# Interface.net
KiCad netlist of a schematic drawn in Altium Designer
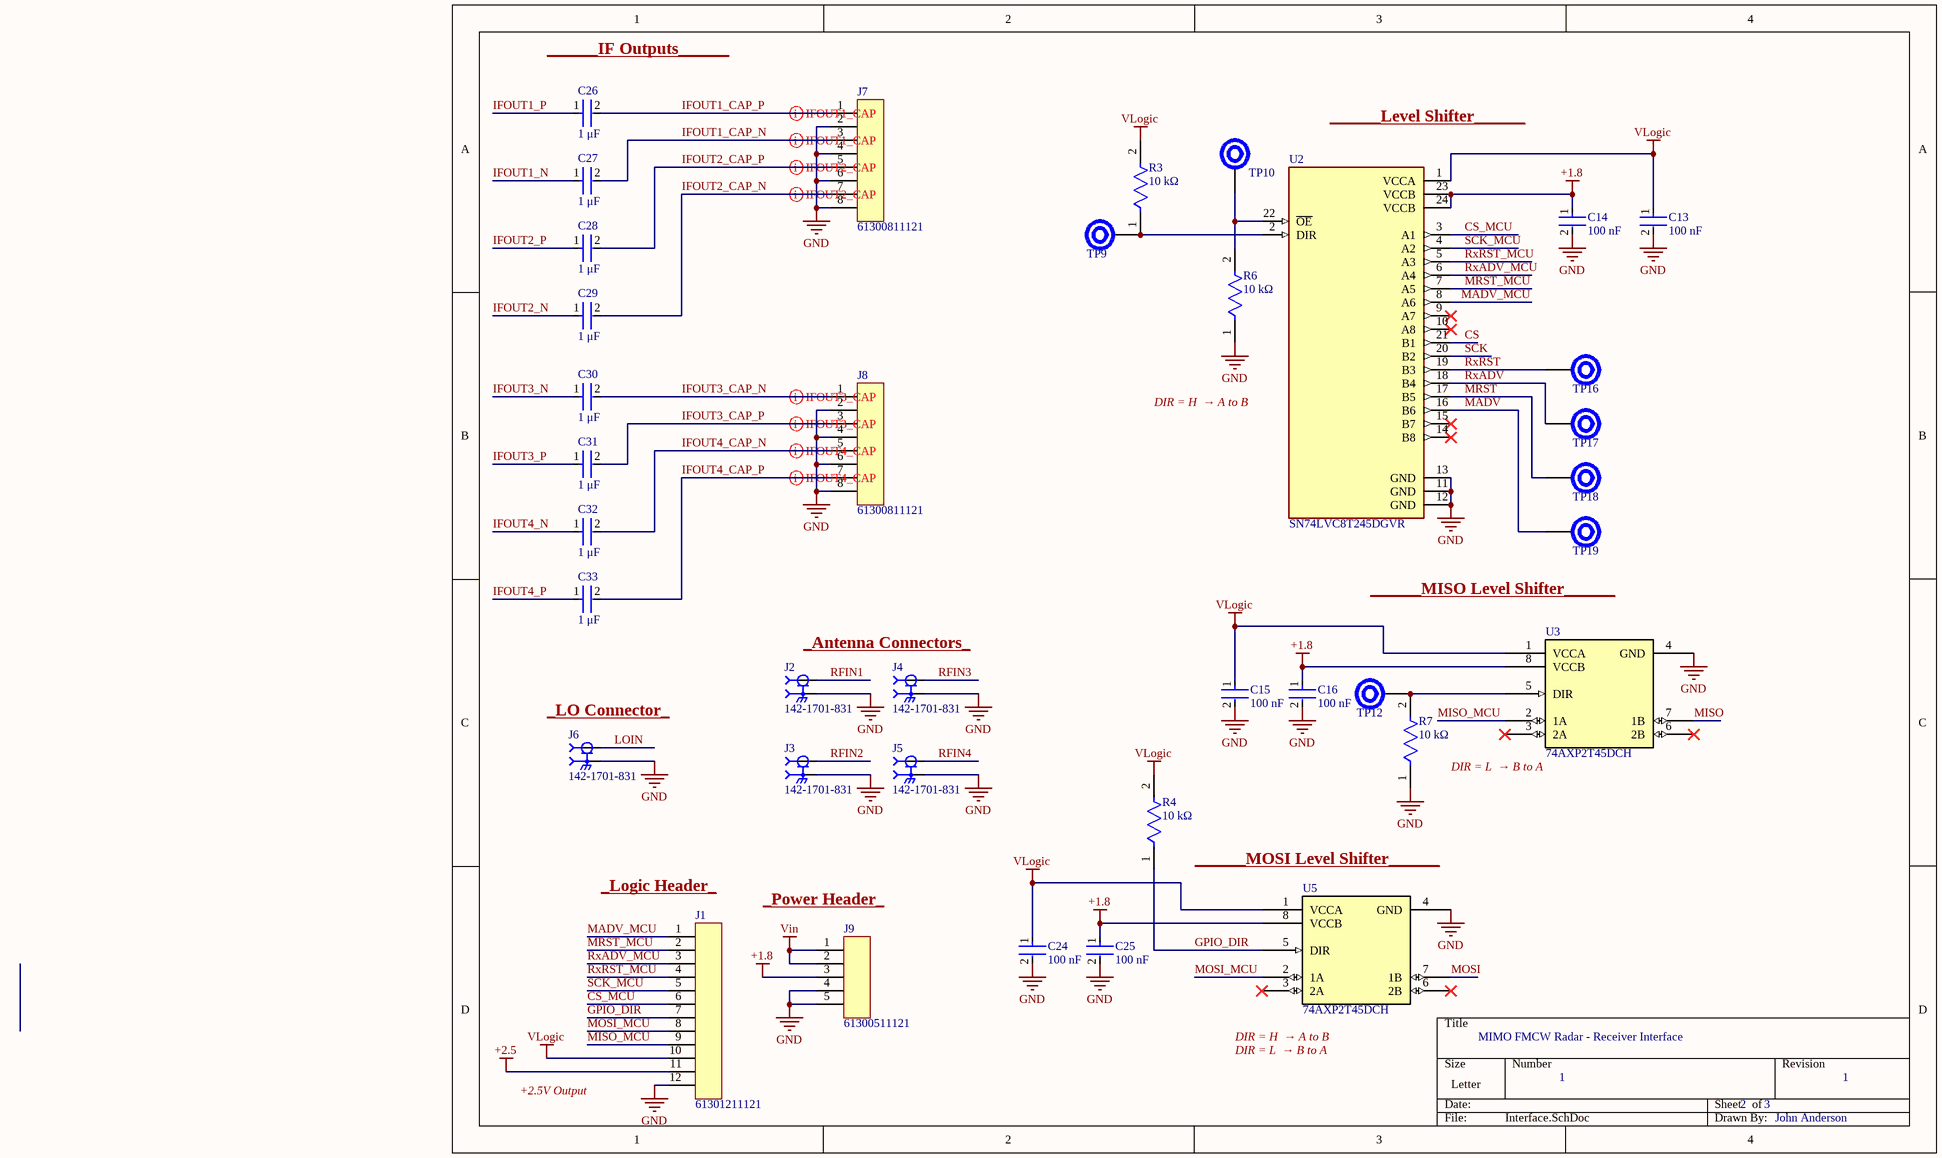
[diagram p0: Interface.SchDoc]

(export (version "E")
  (design (tool "Eeschema 10.0.6"))
  (components
    (comp (ref "C13")
      (value "100 nF")
      (footprint "FP-CGA3E-0_3-0_1-MFG")
      (libsource (lib "Power Pullers") (part "b4654b650e69147ec39a6b967a45e02"))
    )
    (comp (ref "C14")
      (value "100 nF")
      (footprint "FP-CGA3E-0_3-0_1-MFG")
      (libsource (lib "Power Pullers") (part "b4654b650e69147ec39a6b967a45e02"))
    )
    (comp (ref "C15")
      (value "100 nF")
      (footprint "FP-CGA3E-0_3-0_1-MFG")
      (libsource (lib "Power Pullers") (part "b4654b650e69147ec39a6b967a45e02"))
    )
    (comp (ref "C16")
      (value "100 nF")
      (footprint "FP-CGA3E-0_3-0_1-MFG")
      (libsource (lib "Power Pullers") (part "b4654b650e69147ec39a6b967a45e02"))
    )
    (comp (ref "C24")
      (value "100 nF")
      (footprint "FP-CGA3E-0_3-0_1-MFG")
      (libsource (lib "Power Pullers") (part "b4654b650e69147ec39a6b967a45e02"))
    )
    (comp (ref "C25")
      (value "100 nF")
      (footprint "FP-CGA3E-0_3-0_1-MFG")
      (libsource (lib "Power Pullers") (part "b4654b650e69147ec39a6b967a45e02"))
    )
    (comp (ref "C26")
      (value "1 μF")
      (footprint "FP-0603-L_1_6_0_15-W_0_8-MFG")
      (libsource (lib "Power Pullers") (part "11868f565c42a9108669ba33697ecf6"))
    )
    (comp (ref "C27")
      (value "1 μF")
      (footprint "FP-0603-L_1_6_0_15-W_0_8-MFG")
      (libsource (lib "Power Pullers") (part "11868f565c42a9108669ba33697ecf6"))
    )
    (comp (ref "C28")
      (value "1 μF")
      (footprint "FP-0603-L_1_6_0_15-W_0_8-MFG")
      (libsource (lib "Power Pullers") (part "11868f565c42a9108669ba33697ecf6"))
    )
    (comp (ref "C29")
      (value "1 μF")
      (footprint "FP-0603-L_1_6_0_15-W_0_8-MFG")
      (libsource (lib "Power Pullers") (part "11868f565c42a9108669ba33697ecf6"))
    )
    (comp (ref "C30")
      (value "1 μF")
      (footprint "FP-0603-L_1_6_0_15-W_0_8-MFG")
      (libsource (lib "Power Pullers") (part "11868f565c42a9108669ba33697ecf6"))
    )
    (comp (ref "C31")
      (value "1 μF")
      (footprint "FP-0603-L_1_6_0_15-W_0_8-MFG")
      (libsource (lib "Power Pullers") (part "11868f565c42a9108669ba33697ecf6"))
    )
    (comp (ref "C32")
      (value "1 μF")
      (footprint "FP-0603-L_1_6_0_15-W_0_8-MFG")
      (libsource (lib "Power Pullers") (part "11868f565c42a9108669ba33697ecf6"))
    )
    (comp (ref "C33")
      (value "1 μF")
      (footprint "FP-0603-L_1_6_0_15-W_0_8-MFG")
      (libsource (lib "Power Pullers") (part "11868f565c42a9108669ba33697ecf6"))
    )
    (comp (ref "J1")
      (value "61301211121")
      (footprint "61301211121")
      (description "THT Vertical Pin Header WR-PHD, Pitch 2.54 mm, Single Row, 12 pins")
      (libsource (lib "Power Pullers") (part "Header_Male_1R_12P"))
    )
    (comp (ref "J2")
      (value "142-1701-831")
      (footprint "142-1701-831-Footprint-1")
      (description "RF SMA Connector, 1 Contact(s), Female, Board Mount, Surface Mount Terminal, Locking, Jack")
      (libsource (lib "Power Pullers") (part "142-1701-831-Symbol-1"))
    )
    (comp (ref "J3")
      (value "142-1701-831")
      (footprint "142-1701-831-Footprint-1")
      (description "RF SMA Connector, 1 Contact(s), Female, Board Mount, Surface Mount Terminal, Locking, Jack")
      (libsource (lib "Power Pullers") (part "142-1701-831-Symbol-1"))
    )
    (comp (ref "J4")
      (value "142-1701-831")
      (footprint "142-1701-831-Footprint-1")
      (description "RF SMA Connector, 1 Contact(s), Female, Board Mount, Surface Mount Terminal, Locking, Jack")
      (libsource (lib "Power Pullers") (part "142-1701-831-Symbol-1"))
    )
    (comp (ref "J5")
      (value "142-1701-831")
      (footprint "142-1701-831-Footprint-1")
      (description "RF SMA Connector, 1 Contact(s), Female, Board Mount, Surface Mount Terminal, Locking, Jack")
      (libsource (lib "Power Pullers") (part "142-1701-831-Symbol-1"))
    )
    (comp (ref "J6")
      (value "142-1701-831")
      (footprint "142-1701-831-Footprint-1")
      (description "RF SMA Connector, 1 Contact(s), Female, Board Mount, Surface Mount Terminal, Locking, Jack")
      (libsource (lib "Power Pullers") (part "142-1701-831-Symbol-1"))
    )
    (comp (ref "J7")
      (value "61300811121")
      (footprint "61300811121")
      (description "THT Vertical Pin Header WR-PHD, Pitch 2.54 mm, Single Row, 8 pins")
      (libsource (lib "Power Pullers") (part "Header_Male_1R_08P"))
    )
    (comp (ref "J8")
      (value "61300811121")
      (footprint "61300811121")
      (description "THT Vertical Pin Header WR-PHD, Pitch 2.54 mm, Single Row, 8 pins")
      (libsource (lib "Power Pullers") (part "Header_Male_1R_08P"))
    )
    (comp (ref "J9")
      (value "61300511121")
      (footprint "61300511121")
      (description "THT Vertical Pin Header WR-PHD, Pitch 2.54 mm, Single Row, 5 pins")
      (libsource (lib "Power Pullers") (part "Header_Male_1R_05P"))
    )
    (comp (ref "R3")
      (value "10 kΩ")
      (footprint "FP-RC0603-0_55-IPC_C")
      (fields (field (name "POWER") "100mW") (field (name "TOLERANCE") "1%"))
      (libsource (lib "Power Pullers") (part "1029c3af85768c4190bb7ad29bc67b5"))
    )
    (comp (ref "R4")
      (value "10 kΩ")
      (footprint "FP-RC0603-0_55-IPC_C")
      (fields (field (name "POWER") "100mW") (field (name "TOLERANCE") "1%"))
      (libsource (lib "Power Pullers") (part "1029c3af85768c4190bb7ad29bc67b5"))
    )
    (comp (ref "R6")
      (value "10 kΩ")
      (footprint "FP-RC0603-0_55-IPC_C")
      (fields (field (name "POWER") "100mW") (field (name "TOLERANCE") "1%"))
      (libsource (lib "Power Pullers") (part "1029c3af85768c4190bb7ad29bc67b5"))
    )
    (comp (ref "R7")
      (value "10 kΩ")
      (footprint "FP-RC0603-0_55-IPC_C")
      (fields (field (name "POWER") "100mW") (field (name "TOLERANCE") "1%"))
      (libsource (lib "Power Pullers") (part "1029c3af85768c4190bb7ad29bc67b5"))
    )
    (comp (ref "TP9")
      (value "Test Point - 32 mil")
      (footprint "Test Point - 32 mil-Footprint-1")
      (description "32 mil (0.8 mm) test point.")
      (libsource (lib "Power Pullers") (part "Test Point - 32 mil-Symbol-1"))
    )
    (comp (ref "TP10")
      (value "Test Point - 32 mil")
      (footprint "Test Point - 32 mil-Footprint-1")
      (description "32 mil (0.8 mm) test point.")
      (libsource (lib "Power Pullers") (part "Test Point - 32 mil-Symbol-1"))
    )
    (comp (ref "TP12")
      (value "Test Point - 32 mil")
      (footprint "Test Point - 32 mil-Footprint-1")
      (description "32 mil (0.8 mm) test point.")
      (libsource (lib "Power Pullers") (part "Test Point - 32 mil-Symbol-1"))
    )
    (comp (ref "TP16")
      (value "Test Point - 32 mil")
      (footprint "Test Point - 32 mil-Footprint-1")
      (description "32 mil (0.8 mm) test point.")
      (libsource (lib "Power Pullers") (part "Test Point - 32 mil-Symbol-1"))
    )
    (comp (ref "TP17")
      (value "Test Point - 32 mil")
      (footprint "Test Point - 32 mil-Footprint-1")
      (description "32 mil (0.8 mm) test point.")
      (libsource (lib "Power Pullers") (part "Test Point - 32 mil-Symbol-1"))
    )
    (comp (ref "TP18")
      (value "Test Point - 32 mil")
      (footprint "Test Point - 32 mil-Footprint-1")
      (description "32 mil (0.8 mm) test point.")
      (libsource (lib "Power Pullers") (part "Test Point - 32 mil-Symbol-1"))
    )
    (comp (ref "TP19")
      (value "Test Point - 32 mil")
      (footprint "Test Point - 32 mil-Footprint-1")
      (description "32 mil (0.8 mm) test point.")
      (libsource (lib "Power Pullers") (part "Test Point - 32 mil-Symbol-1"))
    )
    (comp (ref "U2")
      (value "SN74LVC8T245DGVR")
      (footprint "SN74LVC8T245DGVR-Footprint-1")
      (description "IC BUS TRANSCVR 8BIT 24TVSOP / Voltage Level Translator 8-CH Bidirectional 24-Pin TVSOP T/R")
      (libsource (lib "Power Pullers") (part "SN74LVC8T245DGVR-Symbol-1"))
    )
    (comp (ref "U3")
      (value "74AXP2T45DCH")
      (footprint "74AXP2T45DCH-Footprint-1")
      (description "Dual Supply Level Translator 2-bit Bidirectional 0.95V to 5.5V 8-Pin VSSOP")
      (libsource (lib "Power Pullers") (part "74AXP2T45DCH-Symbol-1"))
    )
    (comp (ref "U5")
      (value "74AXP2T45DCH")
      (footprint "74AXP2T45DCH-Footprint-1")
      (description "Dual Supply Level Translator 2-bit Bidirectional 0.95V to 5.5V 8-Pin VSSOP")
      (libsource (lib "Power Pullers") (part "74AXP2T45DCH-Symbol-1"))
    )
  )
  (nets
    (net (code "1") (name "+1.8") (class "Default")
      (node (ref "C14") (pin "1") (pinfunction "1_1") (pintype "passive"))
      (node (ref "C16") (pin "1") (pinfunction "1_1") (pintype "passive"))
      (node (ref "C25") (pin "1") (pinfunction "1_1") (pintype "passive"))
      (node (ref "J9") (pin "3") (pinfunction "3_3") (pintype "passive"))
      (node (ref "U2") (pin "23") (pinfunction "VCCB_23") (pintype "power_in"))
      (node (ref "U2") (pin "24") (pinfunction "VCCB_24") (pintype "power_in"))
      (node (ref "U3") (pin "8") (pinfunction "VCCB_8") (pintype "power_in"))
      (node (ref "U5") (pin "8") (pinfunction "VCCB_8") (pintype "power_in"))
    )
    (net (code "2") (name "+2.5") (class "Default")
      (node (ref "J1") (pin "11") (pinfunction "11_11") (pintype "passive"))
    )
    (net (code "3") (name "/CS") (class "Default")
      (node (ref "U2") (pin "21") (pinfunction "B1_21") (pintype "output"))
    )
    (net (code "4") (name "/CS_MCU") (class "Default")
      (node (ref "J1") (pin "6") (pinfunction "6_6") (pintype "passive"))
      (node (ref "U2") (pin "3") (pinfunction "A1_3") (pintype "output"))
    )
    (net (code "5") (name "/GPIO_DIR") (class "Default")
      (node (ref "J1") (pin "7") (pinfunction "7_7") (pintype "passive"))
      (node (ref "R4") (pin "1") (pinfunction "1_1") (pintype "passive"))
      (node (ref "U5") (pin "5") (pinfunction "DIR_5") (pintype "input"))
    )
    (net (code "6") (name "/IFOUT1_CAP_N") (class "Default")
      (node (ref "C27") (pin "2") (pinfunction "2_2") (pintype "passive"))
      (node (ref "J7") (pin "3") (pinfunction "3_3") (pintype "passive"))
    )
    (net (code "7") (name "/IFOUT1_CAP_P") (class "Default")
      (node (ref "C26") (pin "2") (pinfunction "2_2") (pintype "passive"))
      (node (ref "J7") (pin "1") (pinfunction "1_1") (pintype "passive"))
    )
    (net (code "8") (name "/IFOUT1_N") (class "Default")
      (node (ref "C27") (pin "1") (pinfunction "1_1") (pintype "passive"))
    )
    (net (code "9") (name "/IFOUT1_P") (class "Default")
      (node (ref "C26") (pin "1") (pinfunction "1_1") (pintype "passive"))
    )
    (net (code "10") (name "/IFOUT2_CAP_N") (class "Default")
      (node (ref "C29") (pin "2") (pinfunction "2_2") (pintype "passive"))
      (node (ref "J7") (pin "7") (pinfunction "7_7") (pintype "passive"))
    )
    (net (code "11") (name "/IFOUT2_CAP_P") (class "Default")
      (node (ref "C28") (pin "2") (pinfunction "2_2") (pintype "passive"))
      (node (ref "J7") (pin "5") (pinfunction "5_5") (pintype "passive"))
    )
    (net (code "12") (name "/IFOUT2_N") (class "Default")
      (node (ref "C29") (pin "1") (pinfunction "1_1") (pintype "passive"))
    )
    (net (code "13") (name "/IFOUT2_P") (class "Default")
      (node (ref "C28") (pin "1") (pinfunction "1_1") (pintype "passive"))
    )
    (net (code "14") (name "/IFOUT3_CAP_N") (class "Default")
      (node (ref "C30") (pin "2") (pinfunction "2_2") (pintype "passive"))
      (node (ref "J8") (pin "1") (pinfunction "1_1") (pintype "passive"))
    )
    (net (code "15") (name "/IFOUT3_CAP_P") (class "Default")
      (node (ref "C31") (pin "2") (pinfunction "2_2") (pintype "passive"))
      (node (ref "J8") (pin "3") (pinfunction "3_3") (pintype "passive"))
    )
    (net (code "16") (name "/IFOUT3_N") (class "Default")
      (node (ref "C30") (pin "1") (pinfunction "1_1") (pintype "passive"))
    )
    (net (code "17") (name "/IFOUT3_P") (class "Default")
      (node (ref "C31") (pin "1") (pinfunction "1_1") (pintype "passive"))
    )
    (net (code "18") (name "/IFOUT4_CAP_N") (class "Default")
      (node (ref "C32") (pin "2") (pinfunction "2_2") (pintype "passive"))
      (node (ref "J8") (pin "5") (pinfunction "5_5") (pintype "passive"))
    )
    (net (code "19") (name "/IFOUT4_CAP_P") (class "Default")
      (node (ref "C33") (pin "2") (pinfunction "2_2") (pintype "passive"))
      (node (ref "J8") (pin "7") (pinfunction "7_7") (pintype "passive"))
    )
    (net (code "20") (name "/IFOUT4_N") (class "Default")
      (node (ref "C32") (pin "1") (pinfunction "1_1") (pintype "passive"))
    )
    (net (code "21") (name "/IFOUT4_P") (class "Default")
      (node (ref "C33") (pin "1") (pinfunction "1_1") (pintype "passive"))
    )
    (net (code "22") (name "/LOIN") (class "Default")
      (node (ref "J6") (pin "1") (pinfunction "SIG_1") (pintype "passive"))
    )
    (net (code "23") (name "/MADV") (class "Default")
      (node (ref "TP19") (pin "1") (pinfunction "1_1") (pintype "passive"))
      (node (ref "U2") (pin "16") (pinfunction "B6_16") (pintype "output"))
    )
    (net (code "24") (name "/MADV_MCU") (class "Default")
      (node (ref "J1") (pin "1") (pinfunction "1_1") (pintype "passive"))
      (node (ref "U2") (pin "8") (pinfunction "A6_8") (pintype "output"))
    )
    (net (code "25") (name "/MISO") (class "Default")
      (node (ref "U3") (pin "7") (pinfunction "1B_7") (pintype "bidirectional"))
    )
    (net (code "26") (name "/MISO_MCU") (class "Default")
      (node (ref "J1") (pin "9") (pinfunction "9_9") (pintype "passive"))
      (node (ref "U3") (pin "2") (pinfunction "1A_2") (pintype "bidirectional"))
    )
    (net (code "27") (name "/MOSI") (class "Default")
      (node (ref "U5") (pin "7") (pinfunction "1B_7") (pintype "bidirectional"))
    )
    (net (code "28") (name "/MOSI_MCU") (class "Default")
      (node (ref "J1") (pin "8") (pinfunction "8_8") (pintype "passive"))
      (node (ref "U5") (pin "2") (pinfunction "1A_2") (pintype "bidirectional"))
    )
    (net (code "29") (name "/MRST") (class "Default")
      (node (ref "TP18") (pin "1") (pinfunction "1_1") (pintype "passive"))
      (node (ref "U2") (pin "17") (pinfunction "B5_17") (pintype "output"))
    )
    (net (code "30") (name "/MRST_MCU") (class "Default")
      (node (ref "J1") (pin "2") (pinfunction "2_2") (pintype "passive"))
      (node (ref "U2") (pin "7") (pinfunction "A5_7") (pintype "output"))
    )
    (net (code "31") (name "/RFIN1") (class "Default")
      (node (ref "J2") (pin "1") (pinfunction "SIG_1") (pintype "passive"))
    )
    (net (code "32") (name "/RFIN2") (class "Default")
      (node (ref "J3") (pin "1") (pinfunction "SIG_1") (pintype "passive"))
    )
    (net (code "33") (name "/RFIN3") (class "Default")
      (node (ref "J4") (pin "1") (pinfunction "SIG_1") (pintype "passive"))
    )
    (net (code "34") (name "/RFIN4") (class "Default")
      (node (ref "J5") (pin "1") (pinfunction "SIG_1") (pintype "passive"))
    )
    (net (code "35") (name "/RxADV") (class "Default")
      (node (ref "TP17") (pin "1") (pinfunction "1_1") (pintype "passive"))
      (node (ref "U2") (pin "18") (pinfunction "B4_18") (pintype "output"))
    )
    (net (code "36") (name "/RxADV_MCU") (class "Default")
      (node (ref "J1") (pin "3") (pinfunction "3_3") (pintype "passive"))
      (node (ref "U2") (pin "6") (pinfunction "A4_6") (pintype "output"))
    )
    (net (code "37") (name "/RxRST") (class "Default")
      (node (ref "TP16") (pin "1") (pinfunction "1_1") (pintype "passive"))
      (node (ref "U2") (pin "19") (pinfunction "B3_19") (pintype "output"))
    )
    (net (code "38") (name "/RxRST_MCU") (class "Default")
      (node (ref "J1") (pin "4") (pinfunction "4_4") (pintype "passive"))
      (node (ref "U2") (pin "5") (pinfunction "A3_5") (pintype "output"))
    )
    (net (code "39") (name "/SCK") (class "Default")
      (node (ref "U2") (pin "20") (pinfunction "B2_20") (pintype "output"))
    )
    (net (code "40") (name "/SCK_MCU") (class "Default")
      (node (ref "J1") (pin "5") (pinfunction "5_5") (pintype "passive"))
      (node (ref "U2") (pin "4") (pinfunction "A2_4") (pintype "output"))
    )
    (net (code "41") (name "GND") (class "Default")
      (node (ref "C13") (pin "2") (pinfunction "2_2") (pintype "passive"))
      (node (ref "C14") (pin "2") (pinfunction "2_2") (pintype "passive"))
      (node (ref "C15") (pin "2") (pinfunction "2_2") (pintype "passive"))
      (node (ref "C16") (pin "2") (pinfunction "2_2") (pintype "passive"))
      (node (ref "C24") (pin "2") (pinfunction "2_2") (pintype "passive"))
      (node (ref "C25") (pin "2") (pinfunction "2_2") (pintype "passive"))
      (node (ref "J1") (pin "12") (pinfunction "12_12") (pintype "passive"))
      (node (ref "J2") (pin "2") (pinfunction "GND_2") (pintype "power_in"))
      (node (ref "J3") (pin "2") (pinfunction "GND_2") (pintype "power_in"))
      (node (ref "J4") (pin "2") (pinfunction "GND_2") (pintype "power_in"))
      (node (ref "J5") (pin "2") (pinfunction "GND_2") (pintype "power_in"))
      (node (ref "J6") (pin "2") (pinfunction "GND_2") (pintype "power_in"))
      (node (ref "J7") (pin "2") (pinfunction "2_2") (pintype "passive"))
      (node (ref "J7") (pin "4") (pinfunction "4_4") (pintype "passive"))
      (node (ref "J7") (pin "6") (pinfunction "6_6") (pintype "passive"))
      (node (ref "J7") (pin "8") (pinfunction "8_8") (pintype "passive"))
      (node (ref "J8") (pin "2") (pinfunction "2_2") (pintype "passive"))
      (node (ref "J8") (pin "4") (pinfunction "4_4") (pintype "passive"))
      (node (ref "J8") (pin "6") (pinfunction "6_6") (pintype "passive"))
      (node (ref "J8") (pin "8") (pinfunction "8_8") (pintype "passive"))
      (node (ref "J9") (pin "4") (pinfunction "4_4") (pintype "passive"))
      (node (ref "J9") (pin "5") (pinfunction "5_5") (pintype "passive"))
      (node (ref "R6") (pin "1") (pinfunction "1_1") (pintype "passive"))
      (node (ref "R7") (pin "1") (pinfunction "1_1") (pintype "passive"))
      (node (ref "U2") (pin "11") (pinfunction "GND_11") (pintype "power_in"))
      (node (ref "U2") (pin "12") (pinfunction "GND_12") (pintype "power_in"))
      (node (ref "U2") (pin "13") (pinfunction "GND_13") (pintype "power_in"))
      (node (ref "U3") (pin "4") (pinfunction "GND_4") (pintype "power_in"))
      (node (ref "U5") (pin "4") (pinfunction "GND_4") (pintype "power_in"))
    )
    (net (code "42") (name "Net-(U2-DIR)") (class "Default")
      (node (ref "R3") (pin "1") (pinfunction "1_1") (pintype "passive"))
      (node (ref "TP9") (pin "1") (pinfunction "1_1") (pintype "passive"))
      (node (ref "U2") (pin "2") (pinfunction "DIR_2") (pintype "input"))
    )
    (net (code "43") (name "Net-(U2-~{OE})") (class "Default")
      (node (ref "R6") (pin "2") (pinfunction "2_2") (pintype "passive"))
      (node (ref "TP10") (pin "1") (pinfunction "1_1") (pintype "passive"))
      (node (ref "U2") (pin "22") (pinfunction "~{OE}_22") (pintype "input"))
    )
    (net (code "44") (name "Net-(U3-DIR)") (class "Default")
      (node (ref "R7") (pin "2") (pinfunction "2_2") (pintype "passive"))
      (node (ref "TP12") (pin "1") (pinfunction "1_1") (pintype "passive"))
      (node (ref "U3") (pin "5") (pinfunction "DIR_5") (pintype "input"))
    )
    (net (code "45") (name "VLogic") (class "Default")
      (node (ref "C13") (pin "1") (pinfunction "1_1") (pintype "passive"))
      (node (ref "C15") (pin "1") (pinfunction "1_1") (pintype "passive"))
      (node (ref "C24") (pin "1") (pinfunction "1_1") (pintype "passive"))
      (node (ref "J1") (pin "10") (pinfunction "10_10") (pintype "passive"))
      (node (ref "R3") (pin "2") (pinfunction "2_2") (pintype "passive"))
      (node (ref "R4") (pin "2") (pinfunction "2_2") (pintype "passive"))
      (node (ref "U2") (pin "1") (pinfunction "VCCA_1") (pintype "power_in"))
      (node (ref "U3") (pin "1") (pinfunction "VCCA_1") (pintype "power_in"))
      (node (ref "U5") (pin "1") (pinfunction "VCCA_1") (pintype "power_in"))
    )
    (net (code "46") (name "Vin") (class "Default")
      (node (ref "J9") (pin "1") (pinfunction "1_1") (pintype "passive"))
      (node (ref "J9") (pin "2") (pinfunction "2_2") (pintype "passive"))
    )
    (net (code "47") (name "unconnected-(U2-A7-Pad9)") (class "Default")
      (node (ref "U2") (pin "9") (pinfunction "A7_9") (pintype "output+no_connect"))
    )
    (net (code "48") (name "unconnected-(U2-A8-Pad10)") (class "Default")
      (node (ref "U2") (pin "10") (pinfunction "A8_10") (pintype "output+no_connect"))
    )
    (net (code "49") (name "unconnected-(U2-B7-Pad15)") (class "Default")
      (node (ref "U2") (pin "15") (pinfunction "B7_15") (pintype "output+no_connect"))
    )
    (net (code "50") (name "unconnected-(U2-B8-Pad14)") (class "Default")
      (node (ref "U2") (pin "14") (pinfunction "B8_14") (pintype "output+no_connect"))
    )
    (net (code "51") (name "unconnected-(U3-2A-Pad3)") (class "Default")
      (node (ref "U3") (pin "3") (pinfunction "2A_3") (pintype "bidirectional+no_connect"))
    )
    (net (code "52") (name "unconnected-(U3-2B-Pad6)") (class "Default")
      (node (ref "U3") (pin "6") (pinfunction "2B_6") (pintype "bidirectional+no_connect"))
    )
    (net (code "53") (name "unconnected-(U5-2A-Pad3)") (class "Default")
      (node (ref "U5") (pin "3") (pinfunction "2A_3") (pintype "bidirectional+no_connect"))
    )
    (net (code "54") (name "unconnected-(U5-2B-Pad6)") (class "Default")
      (node (ref "U5") (pin "6") (pinfunction "2B_6") (pintype "bidirectional+no_connect"))
    )
  )
)
